# pi.net
KiCad netlist of a schematic drawn in Altium Designer
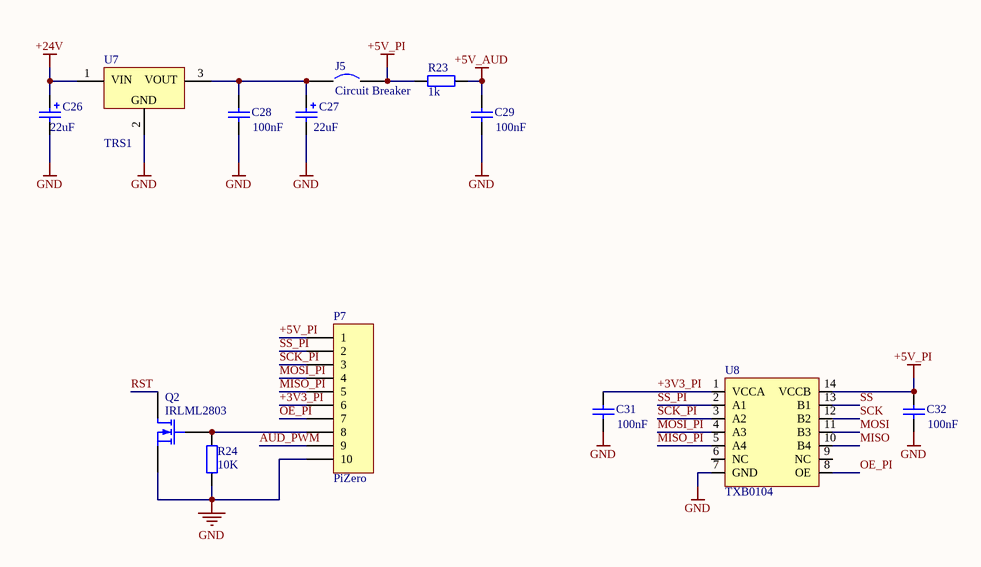
[diagram p0: pi.SchDoc]

(export (version "E")
  (design (tool "Eeschema 10.0.6"))
  (components
    (comp (ref "C26")
      (value "22uF")
      (footprint "EEEFK1H")
      (description "Polarized Capacitor (Axial)")
      (fields (field (name "Comment") "Cap Pol2") (field (name "PUBLISHER") "Altium Limited"))
      (libsource (lib "Miscellaneous Devices") (part "Cap Pol2"))
    )
    (comp (ref "C27")
      (value "22uF")
      (footprint "EEEFK1H")
      (description "Polarized Capacitor (Axial)")
      (fields (field (name "Comment") "Cap Pol2") (field (name "PUBLISHER") "Altium Limited"))
      (libsource (lib "Miscellaneous Devices") (part "Cap Pol2"))
    )
    (comp (ref "C28")
      (value "100nF")
      (footprint "6-0805_M")
      (description "Capacitor")
      (fields (field (name "Comment") "Cap") (field (name "PUBLISHER") "Altium Limited"))
      (libsource (lib "Miscellaneous Devices") (part "Cap"))
    )
    (comp (ref "C29")
      (value "100nF")
      (footprint "6-0805_M")
      (description "Capacitor")
      (fields (field (name "Comment") "Cap") (field (name "PUBLISHER") "Altium Limited"))
      (libsource (lib "Miscellaneous Devices") (part "Cap"))
    )
    (comp (ref "C31")
      (value "100nF")
      (footprint "6-0805_M")
      (description "Capacitor")
      (fields (field (name "Comment") "Cap") (field (name "PUBLISHER") "Altium Limited"))
      (libsource (lib "Miscellaneous Devices") (part "Cap"))
    )
    (comp (ref "C32")
      (value "100nF")
      (footprint "6-0805_M")
      (description "Capacitor")
      (fields (field (name "Comment") "Cap") (field (name "PUBLISHER") "Altium Limited"))
      (libsource (lib "Miscellaneous Devices") (part "Cap"))
    )
    (comp (ref "J5")
      (value "Circuit Breaker")
      (footprint "SOLDER_JUMPER_24mil")
      (fields (field (name "PUBLISHER") "Altium Limited"))
      (libsource (lib "Miscellaneous Devices") (part "Circuit Breaker"))
    )
    (comp (ref "P7")
      (value "PiZero")
      (footprint "HDR1X10")
      (description "Header, 10-Pin")
      (fields (field (name "PUBLISHER") "Altium Limited"))
      (libsource (lib "Miscellaneous Connectors") (part "Header 10"))
    )
    (comp (ref "Q2")
      (value "IRLML2803")
      (footprint "SOT-23_N")
      (description "N-Channel MOSFET")
      (fields (field (name "PUBLISHER") "Altium Limited"))
      (libsource (lib "Miscellaneous Devices") (part "MOSFET-N"))
    )
    (comp (ref "R23")
      (value "1k")
      (footprint "6-0805_M")
      (description "Resistor")
      (fields (field (name "Comment") "Res2") (field (name "PUBLISHER") "Altium Limited"))
      (libsource (lib "") (part "Res2_1"))
    )
    (comp (ref "R24")
      (value "10K")
      (footprint "6-0805_M")
      (description "Resistor")
      (fields (field (name "Comment") "Res2") (field (name "PUBLISHER") "Altium Limited"))
      (libsource (lib "Miscellaneous Devices") (part "Res2"))
    )
    (comp (ref "U7")
      (value "TRS1")
      (footprint "TSR1-2450")
      (description "TSR1-2450 DC/DC Step-Down Converter")
      (libsource (lib "clusterlib") (part "TSR1-2450"))
    )
    (comp (ref "U8")
      (value "TXB0104")
      (footprint "SOIC-14")
      (description "TXB0104 4bit Bidirectional Voltage-Level Translator")
      (libsource (lib "clusterlib") (part "TXB0104"))
    )
  )
  (nets
    (net (code "1") (name "+5V_AUD") (class "Default")
      (node (ref "C29") (pin "2") (pinfunction "2_2") (pintype "passive"))
      (node (ref "R23") (pin "2") (pinfunction "2_2") (pintype "passive"))
    )
    (net (code "2") (name "+5V_PI") (class "Default")
      (node (ref "C32") (pin "2") (pinfunction "2_2") (pintype "passive"))
      (node (ref "J5") (pin "2") (pinfunction "2_2") (pintype "passive"))
      (node (ref "P7") (pin "1") (pinfunction "1_1") (pintype "passive"))
      (node (ref "R23") (pin "1") (pinfunction "1_1") (pintype "passive"))
      (node (ref "U8") (pin "14") (pinfunction "VCCB_14") (pintype "passive"))
    )
    (net (code "3") (name "+24V") (class "Default")
      (node (ref "C26") (pin "1") (pinfunction "1_1") (pintype "passive"))
      (node (ref "U7") (pin "1") (pinfunction "+VIN_1") (pintype "passive"))
    )
    (net (code "4") (name "/+3V3_PI") (class "Default")
      (node (ref "C31") (pin "2") (pinfunction "2_2") (pintype "passive"))
      (node (ref "P7") (pin "6") (pinfunction "6_6") (pintype "passive"))
      (node (ref "U8") (pin "1") (pinfunction "VCCA_1") (pintype "passive"))
    )
    (net (code "5") (name "/AUD_PWM") (class "Default")
      (node (ref "P7") (pin "9") (pinfunction "9_9") (pintype "passive"))
    )
    (net (code "6") (name "/MISO") (class "Default")
      (node (ref "U8") (pin "10") (pinfunction "B4_10") (pintype "passive"))
    )
    (net (code "7") (name "/MISO_PI") (class "Default")
      (node (ref "P7") (pin "5") (pinfunction "5_5") (pintype "passive"))
      (node (ref "U8") (pin "5") (pinfunction "A4_5") (pintype "passive"))
    )
    (net (code "8") (name "/MOSI") (class "Default")
      (node (ref "U8") (pin "11") (pinfunction "B3_11") (pintype "passive"))
    )
    (net (code "9") (name "/MOSI_PI") (class "Default")
      (node (ref "P7") (pin "4") (pinfunction "4_4") (pintype "passive"))
      (node (ref "U8") (pin "4") (pinfunction "A3_4") (pintype "passive"))
    )
    (net (code "10") (name "/OE_PI") (class "Default")
      (node (ref "P7") (pin "7") (pinfunction "7_7") (pintype "passive"))
      (node (ref "U8") (pin "8") (pinfunction "OE_8") (pintype "passive"))
    )
    (net (code "11") (name "/RST") (class "Default")
      (node (ref "Q2") (pin "1") (pinfunction "D_1") (pintype "passive"))
    )
    (net (code "12") (name "/SCK") (class "Default")
      (node (ref "U8") (pin "12") (pinfunction "B2_12") (pintype "passive"))
    )
    (net (code "13") (name "/SCK_PI") (class "Default")
      (node (ref "P7") (pin "3") (pinfunction "3_3") (pintype "passive"))
      (node (ref "U8") (pin "3") (pinfunction "A2_3") (pintype "passive"))
    )
    (net (code "14") (name "/~{SS}") (class "Default")
      (node (ref "U8") (pin "13") (pinfunction "B1_13") (pintype "passive"))
    )
    (net (code "15") (name "/~{SS}_PI") (class "Default")
      (node (ref "P7") (pin "2") (pinfunction "2_2") (pintype "passive"))
      (node (ref "U8") (pin "2") (pinfunction "A1_2") (pintype "passive"))
    )
    (net (code "16") (name "GND") (class "Default")
      (node (ref "C26") (pin "2") (pinfunction "2_2") (pintype "passive"))
      (node (ref "C27") (pin "2") (pinfunction "2_2") (pintype "passive"))
      (node (ref "C28") (pin "1") (pinfunction "1_1") (pintype "passive"))
      (node (ref "C29") (pin "1") (pinfunction "1_1") (pintype "passive"))
      (node (ref "C31") (pin "1") (pinfunction "1_1") (pintype "passive"))
      (node (ref "C32") (pin "1") (pinfunction "1_1") (pintype "passive"))
      (node (ref "P7") (pin "10") (pinfunction "10_10") (pintype "passive"))
      (node (ref "Q2") (pin "3") (pinfunction "S_3") (pintype "passive"))
      (node (ref "R24") (pin "2") (pinfunction "2_2") (pintype "passive"))
      (node (ref "U7") (pin "2") (pinfunction "GND_2") (pintype "passive"))
      (node (ref "U8") (pin "7") (pinfunction "GND_7") (pintype "passive"))
    )
    (net (code "17") (name "Net-(Q2-G)") (class "Default")
      (node (ref "P7") (pin "8") (pinfunction "8_8") (pintype "passive"))
      (node (ref "Q2") (pin "2") (pinfunction "G_2") (pintype "passive"))
      (node (ref "R24") (pin "1") (pinfunction "1_1") (pintype "passive"))
    )
    (net (code "18") (name "Net-(U7-+VOUT)") (class "Default")
      (node (ref "C27") (pin "1") (pinfunction "1_1") (pintype "passive"))
      (node (ref "C28") (pin "2") (pinfunction "2_2") (pintype "passive"))
      (node (ref "J5") (pin "1") (pinfunction "1_1") (pintype "passive"))
      (node (ref "U7") (pin "3") (pinfunction "+VOUT_3") (pintype "passive"))
    )
    (net (code "19") (name "unconnected-(U8-NC-Pad6)") (class "Default")
      (node (ref "U8") (pin "6") (pinfunction "NC_6") (pintype "passive"))
    )
    (net (code "20") (name "unconnected-(U8-NC-Pad9)") (class "Default")
      (node (ref "U8") (pin "9") (pinfunction "NC_9") (pintype "passive"))
    )
  )
)
